# MACH.net
KiCad netlist of a schematic drawn in Altium Designer
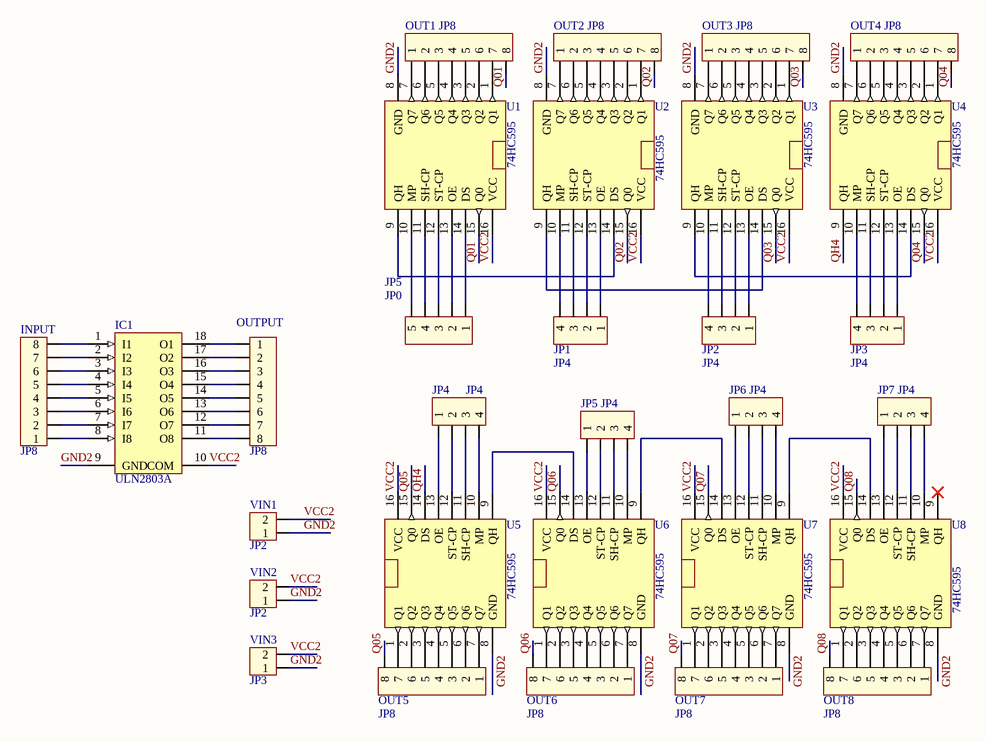
[diagram p0: MACH.SchDoc]

(export (version "E")
  (design (tool "Eeschema 10.0.6"))
  (components
    (comp (ref "IC1")
      (value "ULN2803A")
      (footprint "DIP18/W0.3")
      (description "High-Voltage, High-Current Darlington Array")
      (fields (field (name "PUBLISHER") "Altium Limited"))
      (libsource (lib "syhaunguyen") (part "ULN2803A"))
    )
    (comp (ref "INPUT")
      (value "JP8")
      (footprint "CON8")
      (description "Connector 8")
      (libsource (lib "") (part "Con8_3"))
    )
    (comp (ref "JP0")
      (value "JP5")
      (footprint "CON5")
      (description "Connector 5")
      (libsource (lib "syhaunguyen") (part "Con5"))
    )
    (comp (ref "JP1")
      (value "JP4")
      (footprint "CON4")
      (description "Connector 4")
      (libsource (lib "syhaunguyen") (part "Con4"))
    )
    (comp (ref "JP2")
      (value "JP4")
      (footprint "CON4")
      (description "Connector 4")
      (libsource (lib "syhaunguyen") (part "Con4"))
    )
    (comp (ref "JP3")
      (value "JP4")
      (footprint "CON4")
      (description "Connector 4")
      (libsource (lib "syhaunguyen") (part "Con4"))
    )
    (comp (ref "JP4")
      (value "JP4")
      (footprint "CON4")
      (description "Connector 4")
      (libsource (lib "") (part "Con4_1"))
    )
    (comp (ref "JP5")
      (value "JP4")
      (footprint "CON4")
      (description "Connector 4")
      (libsource (lib "") (part "Con4_1"))
    )
    (comp (ref "JP6")
      (value "JP4")
      (footprint "CON4")
      (description "Connector 4")
      (libsource (lib "") (part "Con4_1"))
    )
    (comp (ref "JP7")
      (value "JP4")
      (footprint "CON4")
      (description "Connector 4")
      (libsource (lib "") (part "Con4_1"))
    )
    (comp (ref "OUT1")
      (value "JP8")
      (footprint "CON8")
      (description "Connector 8")
      (libsource (lib "syhaunguyen") (part "Con8"))
    )
    (comp (ref "OUT2")
      (value "JP8")
      (footprint "CON8")
      (description "Connector 8")
      (libsource (lib "syhaunguyen") (part "Con8"))
    )
    (comp (ref "OUT3")
      (value "JP8")
      (footprint "CON8")
      (description "Connector 8")
      (libsource (lib "syhaunguyen") (part "Con8"))
    )
    (comp (ref "OUT4")
      (value "JP8")
      (footprint "CON8")
      (description "Connector 8")
      (libsource (lib "syhaunguyen") (part "Con8"))
    )
    (comp (ref "OUT5")
      (value "JP8")
      (footprint "CON8")
      (description "Connector 8")
      (libsource (lib "") (part "Con8_1"))
    )
    (comp (ref "OUT6")
      (value "JP8")
      (footprint "CON8")
      (description "Connector 8")
      (libsource (lib "") (part "Con8_1"))
    )
    (comp (ref "OUT7")
      (value "JP8")
      (footprint "CON8")
      (description "Connector 8")
      (libsource (lib "") (part "Con8_1"))
    )
    (comp (ref "OUT8")
      (value "JP8")
      (footprint "CON8")
      (description "Connector 8")
      (libsource (lib "") (part "Con8_1"))
    )
    (comp (ref "OUTPUT")
      (value "JP8")
      (footprint "CON8")
      (description "Connector 8")
      (libsource (lib "") (part "Con8_2"))
    )
    (comp (ref "U1") (value "74HC595") (footprint "SOP16") (libsource (lib "") (part "74HC595_1")))
    (comp (ref "U2") (value "74HC595") (footprint "SOP16") (libsource (lib "") (part "74HC595_1")))
    (comp (ref "U3") (value "74HC595") (footprint "SOP16") (libsource (lib "") (part "74HC595_1")))
    (comp (ref "U4") (value "74HC595") (footprint "SOP16") (libsource (lib "") (part "74HC595_1")))
    (comp (ref "U5") (value "74HC595") (footprint "SOP16") (libsource (lib "74HC595") (part "74HC595")))
    (comp (ref "U6") (value "74HC595") (footprint "SOP16") (libsource (lib "74HC595") (part "74HC595")))
    (comp (ref "U7") (value "74HC595") (footprint "SOP16") (libsource (lib "74HC595") (part "74HC595")))
    (comp (ref "U8") (value "74HC595") (footprint "SOP16") (libsource (lib "74HC595") (part "74HC595")))
    (comp (ref "VIN1")
      (value "JP2")
      (footprint "CON2")
      (description "Connector 2")
      (libsource (lib "syhaunguyen") (part "Con2"))
    )
    (comp (ref "VIN2")
      (value "JP2")
      (footprint "CON2")
      (description "Connector 2")
      (libsource (lib "syhaunguyen") (part "Con2"))
    )
    (comp (ref "VIN3")
      (value "JP3")
      (footprint "CON2")
      (description "Connector 2")
      (libsource (lib "syhaunguyen") (part "Con2"))
    )
  )
  (nets
    (net (code "1") (name "/GND2") (class "Default")
      (node (ref "IC1") (pin "9") (pinfunction "GND_9") (pintype "power_in"))
      (node (ref "U1") (pin "8") (pinfunction "GND_8") (pintype "power_in"))
      (node (ref "U2") (pin "8") (pinfunction "GND_8") (pintype "power_in"))
      (node (ref "U3") (pin "8") (pinfunction "GND_8") (pintype "power_in"))
      (node (ref "U4") (pin "8") (pinfunction "GND_8") (pintype "power_in"))
      (node (ref "U5") (pin "8") (pinfunction "GND_8") (pintype "power_in"))
      (node (ref "U6") (pin "8") (pinfunction "GND_8") (pintype "power_in"))
      (node (ref "U7") (pin "8") (pinfunction "GND_8") (pintype "power_in"))
      (node (ref "U8") (pin "8") (pinfunction "GND_8") (pintype "power_in"))
      (node (ref "VIN1") (pin "1") (pinfunction "1_1") (pintype "passive"))
      (node (ref "VIN2") (pin "1") (pinfunction "1_1") (pintype "passive"))
      (node (ref "VIN3") (pin "1") (pinfunction "1_1") (pintype "passive"))
    )
    (net (code "2") (name "/Q01") (class "Default")
      (node (ref "OUT1") (pin "8") (pinfunction "8_8") (pintype "passive"))
      (node (ref "U1") (pin "15") (pinfunction "Q0_15") (pintype "output"))
    )
    (net (code "3") (name "/Q02") (class "Default")
      (node (ref "OUT2") (pin "8") (pinfunction "8_8") (pintype "passive"))
      (node (ref "U2") (pin "15") (pinfunction "Q0_15") (pintype "output"))
    )
    (net (code "4") (name "/Q03") (class "Default")
      (node (ref "OUT3") (pin "8") (pinfunction "8_8") (pintype "passive"))
      (node (ref "U3") (pin "15") (pinfunction "Q0_15") (pintype "output"))
    )
    (net (code "5") (name "/Q04") (class "Default")
      (node (ref "OUT4") (pin "8") (pinfunction "8_8") (pintype "passive"))
      (node (ref "U4") (pin "15") (pinfunction "Q0_15") (pintype "output"))
    )
    (net (code "6") (name "/Q05") (class "Default")
      (node (ref "OUT5") (pin "8") (pinfunction "8_8") (pintype "passive"))
      (node (ref "U5") (pin "15") (pinfunction "Q0_15") (pintype "output"))
    )
    (net (code "7") (name "/Q06") (class "Default")
      (node (ref "OUT6") (pin "8") (pinfunction "8_8") (pintype "passive"))
      (node (ref "U6") (pin "15") (pinfunction "Q0_15") (pintype "output"))
    )
    (net (code "8") (name "/Q07") (class "Default")
      (node (ref "OUT7") (pin "8") (pinfunction "8_8") (pintype "passive"))
      (node (ref "U7") (pin "15") (pinfunction "Q0_15") (pintype "output"))
    )
    (net (code "9") (name "/Q08") (class "Default")
      (node (ref "OUT8") (pin "8") (pinfunction "8_8") (pintype "passive"))
      (node (ref "U8") (pin "15") (pinfunction "Q0_15") (pintype "output"))
    )
    (net (code "10") (name "/QH4") (class "Default")
      (node (ref "U4") (pin "9") (pinfunction "QH_9") (pintype "passive"))
      (node (ref "U5") (pin "14") (pinfunction "DS_14") (pintype "passive"))
    )
    (net (code "11") (name "/VCC2") (class "Default")
      (node (ref "IC1") (pin "10") (pinfunction "COM_10") (pintype "passive"))
      (node (ref "U1") (pin "16") (pinfunction "VCC_16") (pintype "power_in"))
      (node (ref "U2") (pin "16") (pinfunction "VCC_16") (pintype "power_in"))
      (node (ref "U3") (pin "16") (pinfunction "VCC_16") (pintype "power_in"))
      (node (ref "U4") (pin "16") (pinfunction "VCC_16") (pintype "power_in"))
      (node (ref "U5") (pin "16") (pinfunction "VCC_16") (pintype "power_in"))
      (node (ref "U6") (pin "16") (pinfunction "VCC_16") (pintype "power_in"))
      (node (ref "U7") (pin "16") (pinfunction "VCC_16") (pintype "power_in"))
      (node (ref "U8") (pin "16") (pinfunction "VCC_16") (pintype "power_in"))
      (node (ref "VIN1") (pin "2") (pinfunction "2_2") (pintype "passive"))
      (node (ref "VIN2") (pin "2") (pinfunction "2_2") (pintype "passive"))
      (node (ref "VIN3") (pin "2") (pinfunction "2_2") (pintype "passive"))
    )
    (net (code "12") (name "Net-(IC1-I1)") (class "Default")
      (node (ref "IC1") (pin "1") (pinfunction "I1_1") (pintype "input"))
      (node (ref "INPUT") (pin "8") (pinfunction "8_8") (pintype "passive"))
    )
    (net (code "13") (name "Net-(IC1-I2)") (class "Default")
      (node (ref "IC1") (pin "2") (pinfunction "I2_2") (pintype "input"))
      (node (ref "INPUT") (pin "7") (pinfunction "7_7") (pintype "passive"))
    )
    (net (code "14") (name "Net-(IC1-I3)") (class "Default")
      (node (ref "IC1") (pin "3") (pinfunction "I3_3") (pintype "input"))
      (node (ref "INPUT") (pin "6") (pinfunction "6_6") (pintype "passive"))
    )
    (net (code "15") (name "Net-(IC1-I4)") (class "Default")
      (node (ref "IC1") (pin "4") (pinfunction "I4_4") (pintype "input"))
      (node (ref "INPUT") (pin "5") (pinfunction "5_5") (pintype "passive"))
    )
    (net (code "16") (name "Net-(IC1-I5)") (class "Default")
      (node (ref "IC1") (pin "5") (pinfunction "I5_5") (pintype "input"))
      (node (ref "INPUT") (pin "4") (pinfunction "4_4") (pintype "passive"))
    )
    (net (code "17") (name "Net-(IC1-I6)") (class "Default")
      (node (ref "IC1") (pin "6") (pinfunction "I6_6") (pintype "input"))
      (node (ref "INPUT") (pin "3") (pinfunction "3_3") (pintype "passive"))
    )
    (net (code "18") (name "Net-(IC1-I7)") (class "Default")
      (node (ref "IC1") (pin "7") (pinfunction "I7_7") (pintype "input"))
      (node (ref "INPUT") (pin "2") (pinfunction "2_2") (pintype "passive"))
    )
    (net (code "19") (name "Net-(IC1-I8)") (class "Default")
      (node (ref "IC1") (pin "8") (pinfunction "I8_8") (pintype "input"))
      (node (ref "INPUT") (pin "1") (pinfunction "1_1") (pintype "passive"))
    )
    (net (code "20") (name "Net-(IC1-O1)") (class "Default")
      (node (ref "IC1") (pin "18") (pinfunction "O1_18") (pintype "open_collector"))
      (node (ref "OUTPUT") (pin "1") (pinfunction "1_1") (pintype "passive"))
    )
    (net (code "21") (name "Net-(IC1-O2)") (class "Default")
      (node (ref "IC1") (pin "17") (pinfunction "O2_17") (pintype "open_collector"))
      (node (ref "OUTPUT") (pin "2") (pinfunction "2_2") (pintype "passive"))
    )
    (net (code "22") (name "Net-(IC1-O3)") (class "Default")
      (node (ref "IC1") (pin "16") (pinfunction "O3_16") (pintype "open_collector"))
      (node (ref "OUTPUT") (pin "3") (pinfunction "3_3") (pintype "passive"))
    )
    (net (code "23") (name "Net-(IC1-O4)") (class "Default")
      (node (ref "IC1") (pin "15") (pinfunction "O4_15") (pintype "open_collector"))
      (node (ref "OUTPUT") (pin "4") (pinfunction "4_4") (pintype "passive"))
    )
    (net (code "24") (name "Net-(IC1-O5)") (class "Default")
      (node (ref "IC1") (pin "14") (pinfunction "O5_14") (pintype "open_collector"))
      (node (ref "OUTPUT") (pin "5") (pinfunction "5_5") (pintype "passive"))
    )
    (net (code "25") (name "Net-(IC1-O6)") (class "Default")
      (node (ref "IC1") (pin "13") (pinfunction "O6_13") (pintype "open_collector"))
      (node (ref "OUTPUT") (pin "6") (pinfunction "6_6") (pintype "passive"))
    )
    (net (code "26") (name "Net-(IC1-O7)") (class "Default")
      (node (ref "IC1") (pin "12") (pinfunction "O7_12") (pintype "open_collector"))
      (node (ref "OUTPUT") (pin "7") (pinfunction "7_7") (pintype "passive"))
    )
    (net (code "27") (name "Net-(IC1-O8)") (class "Default")
      (node (ref "IC1") (pin "11") (pinfunction "O8_11") (pintype "open_collector"))
      (node (ref "OUTPUT") (pin "8") (pinfunction "8_8") (pintype "passive"))
    )
    (net (code "28") (name "Net-(U1-DS)") (class "Default")
      (node (ref "JP0") (pin "1") (pinfunction "1_1") (pintype "passive"))
      (node (ref "U1") (pin "14") (pinfunction "DS_14") (pintype "passive"))
    )
    (net (code "29") (name "Net-(U1-MP)") (class "Default")
      (node (ref "JP0") (pin "5") (pinfunction "5_5") (pintype "passive"))
      (node (ref "U1") (pin "10") (pinfunction "MP_10") (pintype "passive"))
    )
    (net (code "30") (name "Net-(U1-OE)") (class "Default")
      (node (ref "JP0") (pin "2") (pinfunction "2_2") (pintype "passive"))
      (node (ref "U1") (pin "13") (pinfunction "OE_13") (pintype "passive"))
    )
    (net (code "31") (name "Net-(U1-Q1)") (class "Default")
      (node (ref "OUT1") (pin "7") (pinfunction "7_7") (pintype "passive"))
      (node (ref "U1") (pin "1") (pinfunction "Q1_1") (pintype "output"))
    )
    (net (code "32") (name "Net-(U1-Q2)") (class "Default")
      (node (ref "OUT1") (pin "6") (pinfunction "6_6") (pintype "passive"))
      (node (ref "U1") (pin "2") (pinfunction "Q2_2") (pintype "output"))
    )
    (net (code "33") (name "Net-(U1-Q3)") (class "Default")
      (node (ref "OUT1") (pin "5") (pinfunction "5_5") (pintype "passive"))
      (node (ref "U1") (pin "3") (pinfunction "Q3_3") (pintype "output"))
    )
    (net (code "34") (name "Net-(U1-Q4)") (class "Default")
      (node (ref "OUT1") (pin "4") (pinfunction "4_4") (pintype "passive"))
      (node (ref "U1") (pin "4") (pinfunction "Q4_4") (pintype "output"))
    )
    (net (code "35") (name "Net-(U1-Q5)") (class "Default")
      (node (ref "OUT1") (pin "3") (pinfunction "3_3") (pintype "passive"))
      (node (ref "U1") (pin "5") (pinfunction "Q5_5") (pintype "output"))
    )
    (net (code "36") (name "Net-(U1-Q6)") (class "Default")
      (node (ref "OUT1") (pin "2") (pinfunction "2_2") (pintype "passive"))
      (node (ref "U1") (pin "6") (pinfunction "Q6_6") (pintype "output"))
    )
    (net (code "37") (name "Net-(U1-Q7)") (class "Default")
      (node (ref "OUT1") (pin "1") (pinfunction "1_1") (pintype "passive"))
      (node (ref "U1") (pin "7") (pinfunction "Q7_7") (pintype "output"))
    )
    (net (code "38") (name "Net-(U1-QH)") (class "Default")
      (node (ref "U1") (pin "9") (pinfunction "QH_9") (pintype "passive"))
      (node (ref "U2") (pin "14") (pinfunction "DS_14") (pintype "passive"))
    )
    (net (code "39") (name "Net-(U1-SH-CP)") (class "Default")
      (node (ref "JP0") (pin "4") (pinfunction "4_4") (pintype "passive"))
      (node (ref "U1") (pin "11") (pinfunction "SH-CP_11") (pintype "passive"))
    )
    (net (code "40") (name "Net-(U1-ST-CP)") (class "Default")
      (node (ref "JP0") (pin "3") (pinfunction "3_3") (pintype "passive"))
      (node (ref "U1") (pin "12") (pinfunction "ST-CP_12") (pintype "passive"))
    )
    (net (code "41") (name "Net-(U2-MP)") (class "Default")
      (node (ref "JP1") (pin "4") (pinfunction "4_4") (pintype "passive"))
      (node (ref "U2") (pin "10") (pinfunction "MP_10") (pintype "passive"))
    )
    (net (code "42") (name "Net-(U2-OE)") (class "Default")
      (node (ref "JP1") (pin "1") (pinfunction "1_1") (pintype "passive"))
      (node (ref "U2") (pin "13") (pinfunction "OE_13") (pintype "passive"))
    )
    (net (code "43") (name "Net-(U2-Q1)") (class "Default")
      (node (ref "OUT2") (pin "7") (pinfunction "7_7") (pintype "passive"))
      (node (ref "U2") (pin "1") (pinfunction "Q1_1") (pintype "output"))
    )
    (net (code "44") (name "Net-(U2-Q2)") (class "Default")
      (node (ref "OUT2") (pin "6") (pinfunction "6_6") (pintype "passive"))
      (node (ref "U2") (pin "2") (pinfunction "Q2_2") (pintype "output"))
    )
    (net (code "45") (name "Net-(U2-Q3)") (class "Default")
      (node (ref "OUT2") (pin "5") (pinfunction "5_5") (pintype "passive"))
      (node (ref "U2") (pin "3") (pinfunction "Q3_3") (pintype "output"))
    )
    (net (code "46") (name "Net-(U2-Q4)") (class "Default")
      (node (ref "OUT2") (pin "4") (pinfunction "4_4") (pintype "passive"))
      (node (ref "U2") (pin "4") (pinfunction "Q4_4") (pintype "output"))
    )
    (net (code "47") (name "Net-(U2-Q5)") (class "Default")
      (node (ref "OUT2") (pin "3") (pinfunction "3_3") (pintype "passive"))
      (node (ref "U2") (pin "5") (pinfunction "Q5_5") (pintype "output"))
    )
    (net (code "48") (name "Net-(U2-Q6)") (class "Default")
      (node (ref "OUT2") (pin "2") (pinfunction "2_2") (pintype "passive"))
      (node (ref "U2") (pin "6") (pinfunction "Q6_6") (pintype "output"))
    )
    (net (code "49") (name "Net-(U2-Q7)") (class "Default")
      (node (ref "OUT2") (pin "1") (pinfunction "1_1") (pintype "passive"))
      (node (ref "U2") (pin "7") (pinfunction "Q7_7") (pintype "output"))
    )
    (net (code "50") (name "Net-(U2-QH)") (class "Default")
      (node (ref "U2") (pin "9") (pinfunction "QH_9") (pintype "passive"))
      (node (ref "U3") (pin "14") (pinfunction "DS_14") (pintype "passive"))
    )
    (net (code "51") (name "Net-(U2-SH-CP)") (class "Default")
      (node (ref "JP1") (pin "3") (pinfunction "3_3") (pintype "passive"))
      (node (ref "U2") (pin "11") (pinfunction "SH-CP_11") (pintype "passive"))
    )
    (net (code "52") (name "Net-(U2-ST-CP)") (class "Default")
      (node (ref "JP1") (pin "2") (pinfunction "2_2") (pintype "passive"))
      (node (ref "U2") (pin "12") (pinfunction "ST-CP_12") (pintype "passive"))
    )
    (net (code "53") (name "Net-(U3-MP)") (class "Default")
      (node (ref "JP2") (pin "4") (pinfunction "4_4") (pintype "passive"))
      (node (ref "U3") (pin "10") (pinfunction "MP_10") (pintype "passive"))
    )
    (net (code "54") (name "Net-(U3-OE)") (class "Default")
      (node (ref "JP2") (pin "1") (pinfunction "1_1") (pintype "passive"))
      (node (ref "U3") (pin "13") (pinfunction "OE_13") (pintype "passive"))
    )
    (net (code "55") (name "Net-(U3-Q1)") (class "Default")
      (node (ref "OUT3") (pin "7") (pinfunction "7_7") (pintype "passive"))
      (node (ref "U3") (pin "1") (pinfunction "Q1_1") (pintype "output"))
    )
    (net (code "56") (name "Net-(U3-Q2)") (class "Default")
      (node (ref "OUT3") (pin "6") (pinfunction "6_6") (pintype "passive"))
      (node (ref "U3") (pin "2") (pinfunction "Q2_2") (pintype "output"))
    )
    (net (code "57") (name "Net-(U3-Q3)") (class "Default")
      (node (ref "OUT3") (pin "5") (pinfunction "5_5") (pintype "passive"))
      (node (ref "U3") (pin "3") (pinfunction "Q3_3") (pintype "output"))
    )
    (net (code "58") (name "Net-(U3-Q4)") (class "Default")
      (node (ref "OUT3") (pin "4") (pinfunction "4_4") (pintype "passive"))
      (node (ref "U3") (pin "4") (pinfunction "Q4_4") (pintype "output"))
    )
    (net (code "59") (name "Net-(U3-Q5)") (class "Default")
      (node (ref "OUT3") (pin "3") (pinfunction "3_3") (pintype "passive"))
      (node (ref "U3") (pin "5") (pinfunction "Q5_5") (pintype "output"))
    )
    (net (code "60") (name "Net-(U3-Q6)") (class "Default")
      (node (ref "OUT3") (pin "2") (pinfunction "2_2") (pintype "passive"))
      (node (ref "U3") (pin "6") (pinfunction "Q6_6") (pintype "output"))
    )
    (net (code "61") (name "Net-(U3-Q7)") (class "Default")
      (node (ref "OUT3") (pin "1") (pinfunction "1_1") (pintype "passive"))
      (node (ref "U3") (pin "7") (pinfunction "Q7_7") (pintype "output"))
    )
    (net (code "62") (name "Net-(U3-QH)") (class "Default")
      (node (ref "U3") (pin "9") (pinfunction "QH_9") (pintype "passive"))
      (node (ref "U4") (pin "14") (pinfunction "DS_14") (pintype "passive"))
    )
    (net (code "63") (name "Net-(U3-SH-CP)") (class "Default")
      (node (ref "JP2") (pin "3") (pinfunction "3_3") (pintype "passive"))
      (node (ref "U3") (pin "11") (pinfunction "SH-CP_11") (pintype "passive"))
    )
    (net (code "64") (name "Net-(U3-ST-CP)") (class "Default")
      (node (ref "JP2") (pin "2") (pinfunction "2_2") (pintype "passive"))
      (node (ref "U3") (pin "12") (pinfunction "ST-CP_12") (pintype "passive"))
    )
    (net (code "65") (name "Net-(U4-MP)") (class "Default")
      (node (ref "JP3") (pin "4") (pinfunction "4_4") (pintype "passive"))
      (node (ref "U4") (pin "10") (pinfunction "MP_10") (pintype "passive"))
    )
    (net (code "66") (name "Net-(U4-OE)") (class "Default")
      (node (ref "JP3") (pin "1") (pinfunction "1_1") (pintype "passive"))
      (node (ref "U4") (pin "13") (pinfunction "OE_13") (pintype "passive"))
    )
    (net (code "67") (name "Net-(U4-Q1)") (class "Default")
      (node (ref "OUT4") (pin "7") (pinfunction "7_7") (pintype "passive"))
      (node (ref "U4") (pin "1") (pinfunction "Q1_1") (pintype "output"))
    )
    (net (code "68") (name "Net-(U4-Q2)") (class "Default")
      (node (ref "OUT4") (pin "6") (pinfunction "6_6") (pintype "passive"))
      (node (ref "U4") (pin "2") (pinfunction "Q2_2") (pintype "output"))
    )
    (net (code "69") (name "Net-(U4-Q3)") (class "Default")
      (node (ref "OUT4") (pin "5") (pinfunction "5_5") (pintype "passive"))
      (node (ref "U4") (pin "3") (pinfunction "Q3_3") (pintype "output"))
    )
    (net (code "70") (name "Net-(U4-Q4)") (class "Default")
      (node (ref "OUT4") (pin "4") (pinfunction "4_4") (pintype "passive"))
      (node (ref "U4") (pin "4") (pinfunction "Q4_4") (pintype "output"))
    )
    (net (code "71") (name "Net-(U4-Q5)") (class "Default")
      (node (ref "OUT4") (pin "3") (pinfunction "3_3") (pintype "passive"))
      (node (ref "U4") (pin "5") (pinfunction "Q5_5") (pintype "output"))
    )
    (net (code "72") (name "Net-(U4-Q6)") (class "Default")
      (node (ref "OUT4") (pin "2") (pinfunction "2_2") (pintype "passive"))
      (node (ref "U4") (pin "6") (pinfunction "Q6_6") (pintype "output"))
    )
    (net (code "73") (name "Net-(U4-Q7)") (class "Default")
      (node (ref "OUT4") (pin "1") (pinfunction "1_1") (pintype "passive"))
      (node (ref "U4") (pin "7") (pinfunction "Q7_7") (pintype "output"))
    )
    (net (code "74") (name "Net-(U4-SH-CP)") (class "Default")
      (node (ref "JP3") (pin "3") (pinfunction "3_3") (pintype "passive"))
      (node (ref "U4") (pin "11") (pinfunction "SH-CP_11") (pintype "passive"))
    )
    (net (code "75") (name "Net-(U4-ST-CP)") (class "Default")
      (node (ref "JP3") (pin "2") (pinfunction "2_2") (pintype "passive"))
      (node (ref "U4") (pin "12") (pinfunction "ST-CP_12") (pintype "passive"))
    )
    (net (code "76") (name "Net-(U5-MP)") (class "Default")
      (node (ref "JP4") (pin "4") (pinfunction "4_4") (pintype "passive"))
      (node (ref "U5") (pin "10") (pinfunction "MP_10") (pintype "passive"))
    )
    (net (code "77") (name "Net-(U5-OE)") (class "Default")
      (node (ref "JP4") (pin "1") (pinfunction "1_1") (pintype "passive"))
      (node (ref "U5") (pin "13") (pinfunction "OE_13") (pintype "passive"))
    )
    (net (code "78") (name "Net-(U5-Q1)") (class "Default")
      (node (ref "OUT5") (pin "7") (pinfunction "7_7") (pintype "passive"))
      (node (ref "U5") (pin "1") (pinfunction "Q1_1") (pintype "output"))
    )
    (net (code "79") (name "Net-(U5-Q2)") (class "Default")
      (node (ref "OUT5") (pin "6") (pinfunction "6_6") (pintype "passive"))
      (node (ref "U5") (pin "2") (pinfunction "Q2_2") (pintype "output"))
    )
    (net (code "80") (name "Net-(U5-Q3)") (class "Default")
      (node (ref "OUT5") (pin "5") (pinfunction "5_5") (pintype "passive"))
      (node (ref "U5") (pin "3") (pinfunction "Q3_3") (pintype "output"))
    )
    (net (code "81") (name "Net-(U5-Q4)") (class "Default")
      (node (ref "OUT5") (pin "4") (pinfunction "4_4") (pintype "passive"))
      (node (ref "U5") (pin "4") (pinfunction "Q4_4") (pintype "output"))
    )
    (net (code "82") (name "Net-(U5-Q5)") (class "Default")
      (node (ref "OUT5") (pin "3") (pinfunction "3_3") (pintype "passive"))
      (node (ref "U5") (pin "5") (pinfunction "Q5_5") (pintype "output"))
    )
    (net (code "83") (name "Net-(U5-Q6)") (class "Default")
      (node (ref "OUT5") (pin "2") (pinfunction "2_2") (pintype "passive"))
      (node (ref "U5") (pin "6") (pinfunction "Q6_6") (pintype "output"))
    )
    (net (code "84") (name "Net-(U5-Q7)") (class "Default")
      (node (ref "OUT5") (pin "1") (pinfunction "1_1") (pintype "passive"))
      (node (ref "U5") (pin "7") (pinfunction "Q7_7") (pintype "output"))
    )
    (net (code "85") (name "Net-(U5-QH)") (class "Default")
      (node (ref "U5") (pin "9") (pinfunction "QH_9") (pintype "passive"))
      (node (ref "U6") (pin "14") (pinfunction "DS_14") (pintype "passive"))
    )
    (net (code "86") (name "Net-(U5-SH-CP)") (class "Default")
      (node (ref "JP4") (pin "3") (pinfunction "3_3") (pintype "passive"))
      (node (ref "U5") (pin "11") (pinfunction "SH-CP_11") (pintype "passive"))
    )
    (net (code "87") (name "Net-(U5-ST-CP)") (class "Default")
      (node (ref "JP4") (pin "2") (pinfunction "2_2") (pintype "passive"))
      (node (ref "U5") (pin "12") (pinfunction "ST-CP_12") (pintype "passive"))
    )
    (net (code "88") (name "Net-(U6-MP)") (class "Default")
      (node (ref "JP5") (pin "4") (pinfunction "4_4") (pintype "passive"))
      (node (ref "U6") (pin "10") (pinfunction "MP_10") (pintype "passive"))
    )
    (net (code "89") (name "Net-(U6-OE)") (class "Default")
      (node (ref "JP5") (pin "1") (pinfunction "1_1") (pintype "passive"))
      (node (ref "U6") (pin "13") (pinfunction "OE_13") (pintype "passive"))
    )
    (net (code "90") (name "Net-(U6-Q1)") (class "Default")
      (node (ref "OUT6") (pin "7") (pinfunction "7_7") (pintype "passive"))
      (node (ref "U6") (pin "1") (pinfunction "Q1_1") (pintype "output"))
    )
    (net (code "91") (name "Net-(U6-Q2)") (class "Default")
      (node (ref "OUT6") (pin "6") (pinfunction "6_6") (pintype "passive"))
      (node (ref "U6") (pin "2") (pinfunction "Q2_2") (pintype "output"))
    )
    (net (code "92") (name "Net-(U6-Q3)") (class "Default")
      (node (ref "OUT6") (pin "5") (pinfunction "5_5") (pintype "passive"))
      (node (ref "U6") (pin "3") (pinfunction "Q3_3") (pintype "output"))
    )
    (net (code "93") (name "Net-(U6-Q4)") (class "Default")
      (node (ref "OUT6") (pin "4") (pinfunction "4_4") (pintype "passive"))
      (node (ref "U6") (pin "4") (pinfunction "Q4_4") (pintype "output"))
    )
    (net (code "94") (name "Net-(U6-Q5)") (class "Default")
      (node (ref "OUT6") (pin "3") (pinfunction "3_3") (pintype "passive"))
      (node (ref "U6") (pin "5") (pinfunction "Q5_5") (pintype "output"))
    )
    (net (code "95") (name "Net-(U6-Q6)") (class "Default")
      (node (ref "OUT6") (pin "2") (pinfunction "2_2") (pintype "passive"))
      (node (ref "U6") (pin "6") (pinfunction "Q6_6") (pintype "output"))
    )
    (net (code "96") (name "Net-(U6-Q7)") (class "Default")
      (node (ref "OUT6") (pin "1") (pinfunction "1_1") (pintype "passive"))
      (node (ref "U6") (pin "7") (pinfunction "Q7_7") (pintype "output"))
    )
    (net (code "97") (name "Net-(U6-QH)") (class "Default")
      (node (ref "U6") (pin "9") (pinfunction "QH_9") (pintype "passive"))
      (node (ref "U7") (pin "14") (pinfunction "DS_14") (pintype "passive"))
    )
    (net (code "98") (name "Net-(U6-SH-CP)") (class "Default")
      (node (ref "JP5") (pin "3") (pinfunction "3_3") (pintype "passive"))
      (node (ref "U6") (pin "11") (pinfunction "SH-CP_11") (pintype "passive"))
    )
    (net (code "99") (name "Net-(U6-ST-CP)") (class "Default")
      (node (ref "JP5") (pin "2") (pinfunction "2_2") (pintype "passive"))
      (node (ref "U6") (pin "12") (pinfunction "ST-CP_12") (pintype "passive"))
    )
    (net (code "100") (name "Net-(U7-MP)") (class "Default")
      (node (ref "JP6") (pin "4") (pinfunction "4_4") (pintype "passive"))
      (node (ref "U7") (pin "10") (pinfunction "MP_10") (pintype "passive"))
    )
    (net (code "101") (name "Net-(U7-OE)") (class "Default")
      (node (ref "JP6") (pin "1") (pinfunction "1_1") (pintype "passive"))
      (node (ref "U7") (pin "13") (pinfunction "OE_13") (pintype "passive"))
    )
    (net (code "102") (name "Net-(U7-Q1)") (class "Default")
      (node (ref "OUT7") (pin "7") (pinfunction "7_7") (pintype "passive"))
      (node (ref "U7") (pin "1") (pinfunction "Q1_1") (pintype "output"))
    )
    (net (code "103") (name "Net-(U7-Q2)") (class "Default")
      (node (ref "OUT7") (pin "6") (pinfunction "6_6") (pintype "passive"))
      (node (ref "U7") (pin "2") (pinfunction "Q2_2") (pintype "output"))
    )
    (net (code "104") (name "Net-(U7-Q3)") (class "Default")
      (node (ref "OUT7") (pin "5") (pinfunction "5_5") (pintype "passive"))
      (node (ref "U7") (pin "3") (pinfunction "Q3_3") (pintype "output"))
    )
    (net (code "105") (name "Net-(U7-Q4)") (class "Default")
      (node (ref "OUT7") (pin "4") (pinfunction "4_4") (pintype "passive"))
      (node (ref "U7") (pin "4") (pinfunction "Q4_4") (pintype "output"))
    )
    (net (code "106") (name "Net-(U7-Q5)") (class "Default")
      (node (ref "OUT7") (pin "3") (pinfunction "3_3") (pintype "passive"))
      (node (ref "U7") (pin "5") (pinfunction "Q5_5") (pintype "output"))
    )
    (net (code "107") (name "Net-(U7-Q6)") (class "Default")
      (node (ref "OUT7") (pin "2") (pinfunction "2_2") (pintype "passive"))
      (node (ref "U7") (pin "6") (pinfunction "Q6_6") (pintype "output"))
    )
    (net (code "108") (name "Net-(U7-Q7)") (class "Default")
      (node (ref "OUT7") (pin "1") (pinfunction "1_1") (pintype "passive"))
      (node (ref "U7") (pin "7") (pinfunction "Q7_7") (pintype "output"))
    )
    (net (code "109") (name "Net-(U7-QH)") (class "Default")
      (node (ref "U7") (pin "9") (pinfunction "QH_9") (pintype "passive"))
      (node (ref "U8") (pin "14") (pinfunction "DS_14") (pintype "passive"))
    )
    (net (code "110") (name "Net-(U7-SH-CP)") (class "Default")
      (node (ref "JP6") (pin "3") (pinfunction "3_3") (pintype "passive"))
      (node (ref "U7") (pin "11") (pinfunction "SH-CP_11") (pintype "passive"))
    )
    (net (code "111") (name "Net-(U7-ST-CP)") (class "Default")
      (node (ref "JP6") (pin "2") (pinfunction "2_2") (pintype "passive"))
      (node (ref "U7") (pin "12") (pinfunction "ST-CP_12") (pintype "passive"))
    )
    (net (code "112") (name "Net-(U8-MP)") (class "Default")
      (node (ref "JP7") (pin "4") (pinfunction "4_4") (pintype "passive"))
      (node (ref "U8") (pin "10") (pinfunction "MP_10") (pintype "passive"))
    )
    (net (code "113") (name "Net-(U8-OE)") (class "Default")
      (node (ref "JP7") (pin "1") (pinfunction "1_1") (pintype "passive"))
      (node (ref "U8") (pin "13") (pinfunction "OE_13") (pintype "passive"))
    )
    (net (code "114") (name "Net-(U8-Q1)") (class "Default")
      (node (ref "OUT8") (pin "7") (pinfunction "7_7") (pintype "passive"))
      (node (ref "U8") (pin "1") (pinfunction "Q1_1") (pintype "output"))
    )
    (net (code "115") (name "Net-(U8-Q2)") (class "Default")
      (node (ref "OUT8") (pin "6") (pinfunction "6_6") (pintype "passive"))
      (node (ref "U8") (pin "2") (pinfunction "Q2_2") (pintype "output"))
    )
    (net (code "116") (name "Net-(U8-Q3)") (class "Default")
      (node (ref "OUT8") (pin "5") (pinfunction "5_5") (pintype "passive"))
      (node (ref "U8") (pin "3") (pinfunction "Q3_3") (pintype "output"))
    )
    (net (code "117") (name "Net-(U8-Q4)") (class "Default")
      (node (ref "OUT8") (pin "4") (pinfunction "4_4") (pintype "passive"))
      (node (ref "U8") (pin "4") (pinfunction "Q4_4") (pintype "output"))
    )
    (net (code "118") (name "Net-(U8-Q5)") (class "Default")
      (node (ref "OUT8") (pin "3") (pinfunction "3_3") (pintype "passive"))
      (node (ref "U8") (pin "5") (pinfunction "Q5_5") (pintype "output"))
    )
    (net (code "119") (name "Net-(U8-Q6)") (class "Default")
      (node (ref "OUT8") (pin "2") (pinfunction "2_2") (pintype "passive"))
      (node (ref "U8") (pin "6") (pinfunction "Q6_6") (pintype "output"))
    )
    (net (code "120") (name "Net-(U8-Q7)") (class "Default")
      (node (ref "OUT8") (pin "1") (pinfunction "1_1") (pintype "passive"))
      (node (ref "U8") (pin "7") (pinfunction "Q7_7") (pintype "output"))
    )
    (net (code "121") (name "Net-(U8-SH-CP)") (class "Default")
      (node (ref "JP7") (pin "3") (pinfunction "3_3") (pintype "passive"))
      (node (ref "U8") (pin "11") (pinfunction "SH-CP_11") (pintype "passive"))
    )
    (net (code "122") (name "Net-(U8-ST-CP)") (class "Default")
      (node (ref "JP7") (pin "2") (pinfunction "2_2") (pintype "passive"))
      (node (ref "U8") (pin "12") (pinfunction "ST-CP_12") (pintype "passive"))
    )
    (net (code "123") (name "unconnected-(U8-QH-Pad9)") (class "Default")
      (node (ref "U8") (pin "9") (pinfunction "QH_9") (pintype "passive+no_connect"))
    )
  )
)
